# DSP2.net
KiCad netlist of a schematic drawn in Altium Designer
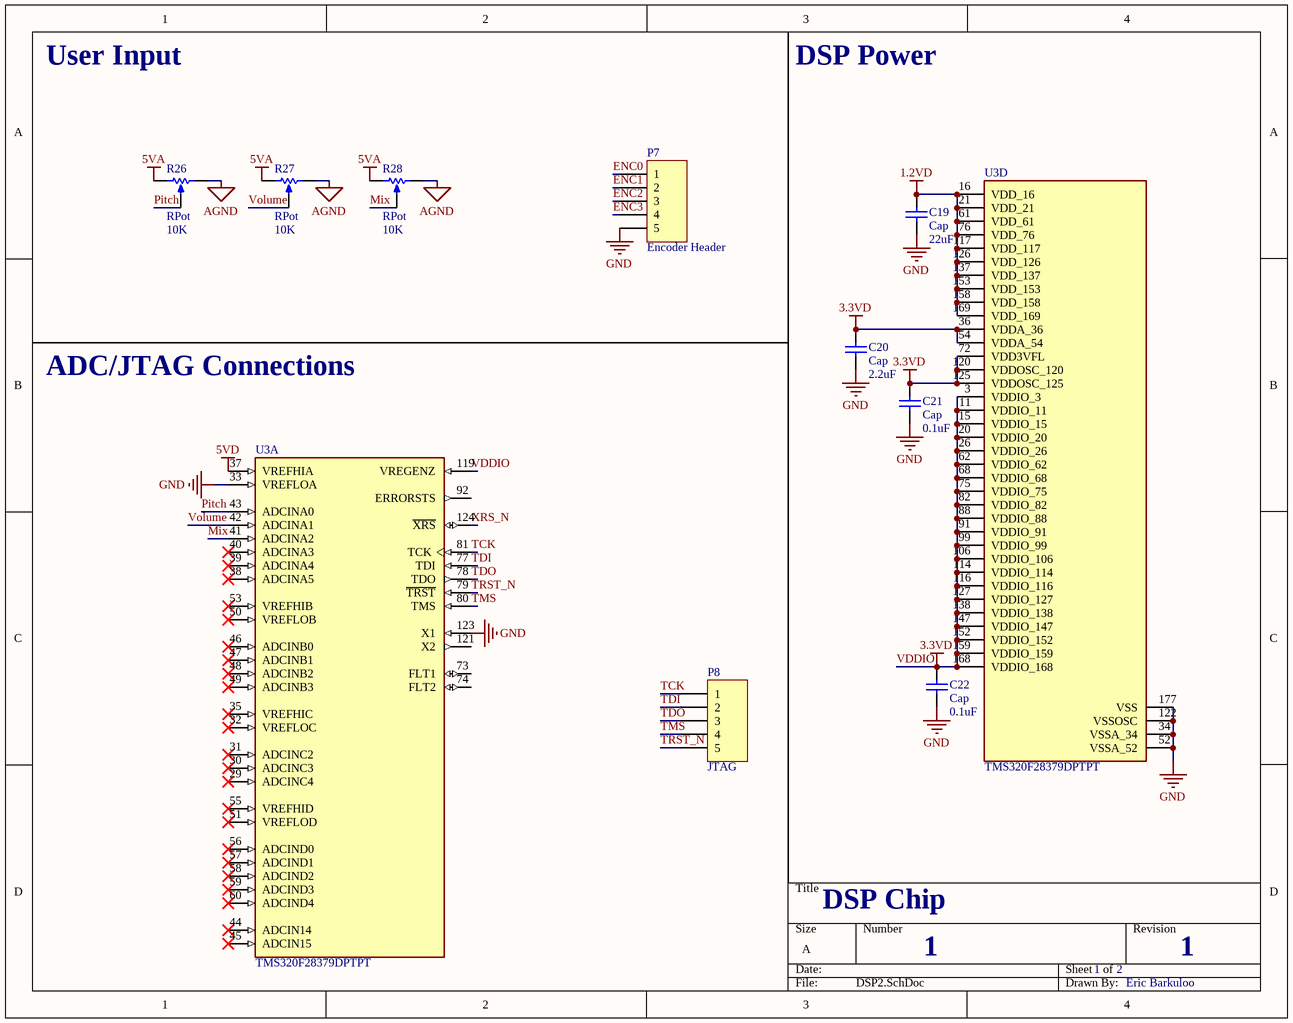
[diagram p0: DSP2.SchDoc]

(export (version "E")
  (design (tool "Eeschema 10.0.6"))
  (components
    (comp (ref "C19")
      (value "Cap")
      (footprint "RAD-0.3")
      (description "Capacitor")
      (fields (field (name "ALTIUM_VALUE") "22uF") (field (name "PUBLISHER") "Altium Limited"))
      (libsource (lib "Miscellaneous Devices") (part "Cap"))
    )
    (comp (ref "C20")
      (value "Cap")
      (footprint "RAD-0.3")
      (description "Capacitor")
      (fields (field (name "ALTIUM_VALUE") "2.2uF") (field (name "PUBLISHER") "Altium Limited"))
      (libsource (lib "Miscellaneous Devices") (part "Cap"))
    )
    (comp (ref "C21")
      (value "Cap")
      (footprint "RAD-0.3")
      (description "Capacitor")
      (fields (field (name "ALTIUM_VALUE") "0.1uF") (field (name "PUBLISHER") "Altium Limited"))
      (libsource (lib "Miscellaneous Devices") (part "Cap"))
    )
    (comp (ref "C22")
      (value "Cap")
      (footprint "RAD-0.3")
      (description "Capacitor")
      (fields (field (name "ALTIUM_VALUE") "0.1uF") (field (name "PUBLISHER") "Altium Limited"))
      (libsource (lib "Miscellaneous Devices") (part "Cap"))
    )
    (comp (ref "P7")
      (value "Encoder Header")
      (footprint "HDR1X5")
      (description "Header, 5-Pin")
      (fields (field (name "PUBLISHER") "Altium Limited"))
      (libsource (lib "Miscellaneous Connectors") (part "Header 5"))
    )
    (comp (ref "P8")
      (value "JTAG")
      (footprint "HDR1X5")
      (description "Header, 5-Pin")
      (fields (field (name "PUBLISHER") "Altium Limited"))
      (libsource (lib "Miscellaneous Connectors") (part "Header 5"))
    )
    (comp (ref "R26")
      (value "RPot")
      (footprint "VR5")
      (description "Potentiometer")
      (fields (field (name "ALTIUM_VALUE") "10K") (field (name "PUBLISHER") "Altium Limited"))
      (libsource (lib "Miscellaneous Devices") (part "RPot"))
    )
    (comp (ref "R27")
      (value "RPot")
      (footprint "VR5")
      (description "Potentiometer")
      (fields (field (name "ALTIUM_VALUE") "10K") (field (name "PUBLISHER") "Altium Limited"))
      (libsource (lib "Miscellaneous Devices") (part "RPot"))
    )
    (comp (ref "R28")
      (value "RPot")
      (footprint "VR5")
      (description "Potentiometer")
      (fields (field (name "ALTIUM_VALUE") "10K") (field (name "PUBLISHER") "Altium Limited"))
      (libsource (lib "Miscellaneous Devices") (part "RPot"))
    )
    (comp (ref "U3")
      (value "TMS320F28379DPTPT")
      (footprint "IC_TMS320F28379DPTPT")
      (libsource (lib "TMS320F28379DPTPT") (part "TMS320F28379DPTPT"))
    )
  )
  (nets
    (net (code "1") (name "/ENC0") (class "Default")
      (node (ref "P7") (pin "1") (pinfunction "1_1") (pintype "passive"))
    )
    (net (code "2") (name "/ENC1") (class "Default")
      (node (ref "P7") (pin "2") (pinfunction "2_2") (pintype "passive"))
    )
    (net (code "3") (name "/ENC2") (class "Default")
      (node (ref "P7") (pin "3") (pinfunction "3_3") (pintype "passive"))
    )
    (net (code "4") (name "/ENC3") (class "Default")
      (node (ref "P7") (pin "4") (pinfunction "4_4") (pintype "passive"))
    )
    (net (code "5") (name "/Mix") (class "Default")
      (node (ref "R28") (pin "3") (pinfunction "TAP_3") (pintype "passive"))
      (node (ref "U3") (pin "41") (pinfunction "ADCINA2_41") (pintype "input"))
    )
    (net (code "6") (name "/Pitch") (class "Default")
      (node (ref "R26") (pin "3") (pinfunction "TAP_3") (pintype "passive"))
      (node (ref "U3") (pin "43") (pinfunction "ADCINA0_43") (pintype "input"))
    )
    (net (code "7") (name "/TCK") (class "Default")
      (node (ref "P8") (pin "1") (pinfunction "1_1") (pintype "passive"))
      (node (ref "U3") (pin "81") (pinfunction "TCK_81") (pintype "input"))
    )
    (net (code "8") (name "/TDI") (class "Default")
      (node (ref "P8") (pin "2") (pinfunction "2_2") (pintype "passive"))
      (node (ref "U3") (pin "77") (pinfunction "TDI_77") (pintype "input"))
    )
    (net (code "9") (name "/TDO") (class "Default")
      (node (ref "P8") (pin "3") (pinfunction "3_3") (pintype "passive"))
      (node (ref "U3") (pin "78") (pinfunction "TDO_78") (pintype "output"))
    )
    (net (code "10") (name "/TMS") (class "Default")
      (node (ref "P8") (pin "4") (pinfunction "4_4") (pintype "passive"))
      (node (ref "U3") (pin "80") (pinfunction "TMS_80") (pintype "input"))
    )
    (net (code "11") (name "/TRST_N") (class "Default")
      (node (ref "P8") (pin "5") (pinfunction "5_5") (pintype "passive"))
      (node (ref "U3") (pin "79") (pinfunction "~{TRST}_79") (pintype "input"))
    )
    (net (code "12") (name "/Volume") (class "Default")
      (node (ref "R27") (pin "3") (pinfunction "TAP_3") (pintype "passive"))
      (node (ref "U3") (pin "42") (pinfunction "ADCINA1_42") (pintype "input"))
    )
    (net (code "13") (name "/XRS_N") (class "Default")
      (node (ref "U3") (pin "124") (pinfunction "~{XRS}_124") (pintype "bidirectional"))
    )
    (net (code "14") (name "1.2VD") (class "Default")
      (node (ref "C19") (pin "2") (pinfunction "2_2") (pintype "passive"))
      (node (ref "U3") (pin "117") (pinfunction "VDD_117_117") (pintype "power_in"))
      (node (ref "U3") (pin "126") (pinfunction "VDD_126_126") (pintype "power_in"))
      (node (ref "U3") (pin "137") (pinfunction "VDD_137_137") (pintype "power_in"))
      (node (ref "U3") (pin "153") (pinfunction "VDD_153_153") (pintype "power_in"))
      (node (ref "U3") (pin "158") (pinfunction "VDD_158_158") (pintype "power_in"))
      (node (ref "U3") (pin "16") (pinfunction "VDD_16_16") (pintype "power_in"))
      (node (ref "U3") (pin "169") (pinfunction "VDD_169_169") (pintype "power_in"))
      (node (ref "U3") (pin "21") (pinfunction "VDD_21_21") (pintype "power_in"))
      (node (ref "U3") (pin "61") (pinfunction "VDD_61_61") (pintype "power_in"))
      (node (ref "U3") (pin "76") (pinfunction "VDD_76_76") (pintype "power_in"))
    )
    (net (code "15") (name "3.3VD") (class "Default")
      (node (ref "C20") (pin "2") (pinfunction "2_2") (pintype "passive"))
      (node (ref "C21") (pin "2") (pinfunction "2_2") (pintype "passive"))
      (node (ref "C22") (pin "2") (pinfunction "2_2") (pintype "passive"))
      (node (ref "U3") (pin "106") (pinfunction "VDDIO_106_106") (pintype "power_in"))
      (node (ref "U3") (pin "11") (pinfunction "VDDIO_11_11") (pintype "power_in"))
      (node (ref "U3") (pin "114") (pinfunction "VDDIO_114_114") (pintype "power_in"))
      (node (ref "U3") (pin "116") (pinfunction "VDDIO_116_116") (pintype "power_in"))
      (node (ref "U3") (pin "119") (pinfunction "VREGENZ_119") (pintype "input"))
      (node (ref "U3") (pin "120") (pinfunction "VDDOSC_120_120") (pintype "power_in"))
      (node (ref "U3") (pin "125") (pinfunction "VDDOSC_125_125") (pintype "power_in"))
      (node (ref "U3") (pin "127") (pinfunction "VDDIO_127_127") (pintype "power_in"))
      (node (ref "U3") (pin "138") (pinfunction "VDDIO_138_138") (pintype "power_in"))
      (node (ref "U3") (pin "147") (pinfunction "VDDIO_147_147") (pintype "power_in"))
      (node (ref "U3") (pin "15") (pinfunction "VDDIO_15_15") (pintype "power_in"))
      (node (ref "U3") (pin "152") (pinfunction "VDDIO_152_152") (pintype "power_in"))
      (node (ref "U3") (pin "159") (pinfunction "VDDIO_159_159") (pintype "power_in"))
      (node (ref "U3") (pin "168") (pinfunction "VDDIO_168_168") (pintype "power_in"))
      (node (ref "U3") (pin "20") (pinfunction "VDDIO_20_20") (pintype "power_in"))
      (node (ref "U3") (pin "26") (pinfunction "VDDIO_26_26") (pintype "power_in"))
      (node (ref "U3") (pin "3") (pinfunction "VDDIO_3_3") (pintype "power_in"))
      (node (ref "U3") (pin "36") (pinfunction "VDDA_36_36") (pintype "power_in"))
      (node (ref "U3") (pin "54") (pinfunction "VDDA_54_54") (pintype "power_in"))
      (node (ref "U3") (pin "62") (pinfunction "VDDIO_62_62") (pintype "power_in"))
      (node (ref "U3") (pin "68") (pinfunction "VDDIO_68_68") (pintype "power_in"))
      (node (ref "U3") (pin "72") (pinfunction "VDD3VFL_72") (pintype "power_in"))
      (node (ref "U3") (pin "75") (pinfunction "VDDIO_75_75") (pintype "power_in"))
      (node (ref "U3") (pin "82") (pinfunction "VDDIO_82_82") (pintype "power_in"))
      (node (ref "U3") (pin "88") (pinfunction "VDDIO_88_88") (pintype "power_in"))
      (node (ref "U3") (pin "91") (pinfunction "VDDIO_91_91") (pintype "power_in"))
      (node (ref "U3") (pin "99") (pinfunction "VDDIO_99_99") (pintype "power_in"))
    )
    (net (code "16") (name "5VA") (class "Default")
      (node (ref "R26") (pin "1") (pinfunction "TOP_1") (pintype "passive"))
      (node (ref "R27") (pin "1") (pinfunction "TOP_1") (pintype "passive"))
      (node (ref "R28") (pin "1") (pinfunction "TOP_1") (pintype "passive"))
    )
    (net (code "17") (name "5VD") (class "Default")
      (node (ref "U3") (pin "37") (pinfunction "VREFHIA_37") (pintype "input"))
    )
    (net (code "18") (name "AGND") (class "Default")
      (node (ref "R26") (pin "2") (pinfunction "BOT_2") (pintype "passive"))
      (node (ref "R27") (pin "2") (pinfunction "BOT_2") (pintype "passive"))
      (node (ref "R28") (pin "2") (pinfunction "BOT_2") (pintype "passive"))
    )
    (net (code "19") (name "GND") (class "Default")
      (node (ref "C19") (pin "1") (pinfunction "1_1") (pintype "passive"))
      (node (ref "C20") (pin "1") (pinfunction "1_1") (pintype "passive"))
      (node (ref "C21") (pin "1") (pinfunction "1_1") (pintype "passive"))
      (node (ref "C22") (pin "1") (pinfunction "1_1") (pintype "passive"))
      (node (ref "P7") (pin "5") (pinfunction "5_5") (pintype "passive"))
      (node (ref "U3") (pin "122") (pinfunction "VSSOSC_122") (pintype "power_in"))
      (node (ref "U3") (pin "123") (pinfunction "X1_123") (pintype "input"))
      (node (ref "U3") (pin "177") (pinfunction "VSS_177") (pintype "power_in"))
      (node (ref "U3") (pin "33") (pinfunction "VREFLOA_33") (pintype "input"))
      (node (ref "U3") (pin "34") (pinfunction "VSSA_34_34") (pintype "power_in"))
      (node (ref "U3") (pin "52") (pinfunction "VSSA_52_52") (pintype "power_in"))
    )
    (net (code "20") (name "unconnected-(U3A-ADCIN14-Pad44)") (class "Default")
      (node (ref "U3") (pin "44") (pinfunction "ADCIN14_44") (pintype "input+no_connect"))
    )
    (net (code "21") (name "unconnected-(U3A-ADCIN15-Pad45)") (class "Default")
      (node (ref "U3") (pin "45") (pinfunction "ADCIN15_45") (pintype "input+no_connect"))
    )
    (net (code "22") (name "unconnected-(U3A-ADCINA3-Pad40)") (class "Default")
      (node (ref "U3") (pin "40") (pinfunction "ADCINA3_40") (pintype "input+no_connect"))
    )
    (net (code "23") (name "unconnected-(U3A-ADCINA4-Pad39)") (class "Default")
      (node (ref "U3") (pin "39") (pinfunction "ADCINA4_39") (pintype "input+no_connect"))
    )
    (net (code "24") (name "unconnected-(U3A-ADCINA5-Pad38)") (class "Default")
      (node (ref "U3") (pin "38") (pinfunction "ADCINA5_38") (pintype "input+no_connect"))
    )
    (net (code "25") (name "unconnected-(U3A-ADCINB0-Pad46)") (class "Default")
      (node (ref "U3") (pin "46") (pinfunction "ADCINB0_46") (pintype "input+no_connect"))
    )
    (net (code "26") (name "unconnected-(U3A-ADCINB1-Pad47)") (class "Default")
      (node (ref "U3") (pin "47") (pinfunction "ADCINB1_47") (pintype "input+no_connect"))
    )
    (net (code "27") (name "unconnected-(U3A-ADCINB2-Pad48)") (class "Default")
      (node (ref "U3") (pin "48") (pinfunction "ADCINB2_48") (pintype "input+no_connect"))
    )
    (net (code "28") (name "unconnected-(U3A-ADCINB3-Pad49)") (class "Default")
      (node (ref "U3") (pin "49") (pinfunction "ADCINB3_49") (pintype "input+no_connect"))
    )
    (net (code "29") (name "unconnected-(U3A-ADCINC2-Pad31)") (class "Default")
      (node (ref "U3") (pin "31") (pinfunction "ADCINC2_31") (pintype "input+no_connect"))
    )
    (net (code "30") (name "unconnected-(U3A-ADCINC3-Pad30)") (class "Default")
      (node (ref "U3") (pin "30") (pinfunction "ADCINC3_30") (pintype "input+no_connect"))
    )
    (net (code "31") (name "unconnected-(U3A-ADCINC4-Pad29)") (class "Default")
      (node (ref "U3") (pin "29") (pinfunction "ADCINC4_29") (pintype "input+no_connect"))
    )
    (net (code "32") (name "unconnected-(U3A-ADCIND0-Pad56)") (class "Default")
      (node (ref "U3") (pin "56") (pinfunction "ADCIND0_56") (pintype "input+no_connect"))
    )
    (net (code "33") (name "unconnected-(U3A-ADCIND1-Pad57)") (class "Default")
      (node (ref "U3") (pin "57") (pinfunction "ADCIND1_57") (pintype "input+no_connect"))
    )
    (net (code "34") (name "unconnected-(U3A-ADCIND2-Pad58)") (class "Default")
      (node (ref "U3") (pin "58") (pinfunction "ADCIND2_58") (pintype "input+no_connect"))
    )
    (net (code "35") (name "unconnected-(U3A-ADCIND3-Pad59)") (class "Default")
      (node (ref "U3") (pin "59") (pinfunction "ADCIND3_59") (pintype "input+no_connect"))
    )
    (net (code "36") (name "unconnected-(U3A-ADCIND4-Pad60)") (class "Default")
      (node (ref "U3") (pin "60") (pinfunction "ADCIND4_60") (pintype "input+no_connect"))
    )
    (net (code "37") (name "unconnected-(U3A-ERRORSTS-Pad92)") (class "Default")
      (node (ref "U3") (pin "92") (pinfunction "ERRORSTS_92") (pintype "output"))
    )
    (net (code "38") (name "unconnected-(U3A-FLT1-Pad73)") (class "Default")
      (node (ref "U3") (pin "73") (pinfunction "FLT1_73") (pintype "bidirectional"))
    )
    (net (code "39") (name "unconnected-(U3A-FLT2-Pad74)") (class "Default")
      (node (ref "U3") (pin "74") (pinfunction "FLT2_74") (pintype "bidirectional"))
    )
    (net (code "40") (name "unconnected-(U3A-VREFHIB-Pad53)") (class "Default")
      (node (ref "U3") (pin "53") (pinfunction "VREFHIB_53") (pintype "input+no_connect"))
    )
    (net (code "41") (name "unconnected-(U3A-VREFHIC-Pad35)") (class "Default")
      (node (ref "U3") (pin "35") (pinfunction "VREFHIC_35") (pintype "input+no_connect"))
    )
    (net (code "42") (name "unconnected-(U3A-VREFHID-Pad55)") (class "Default")
      (node (ref "U3") (pin "55") (pinfunction "VREFHID_55") (pintype "input+no_connect"))
    )
    (net (code "43") (name "unconnected-(U3A-VREFLOB-Pad50)") (class "Default")
      (node (ref "U3") (pin "50") (pinfunction "VREFLOB_50") (pintype "input+no_connect"))
    )
    (net (code "44") (name "unconnected-(U3A-VREFLOC-Pad32)") (class "Default")
      (node (ref "U3") (pin "32") (pinfunction "VREFLOC_32") (pintype "input+no_connect"))
    )
    (net (code "45") (name "unconnected-(U3A-VREFLOD-Pad51)") (class "Default")
      (node (ref "U3") (pin "51") (pinfunction "VREFLOD_51") (pintype "input+no_connect"))
    )
    (net (code "46") (name "unconnected-(U3A-X2-Pad121)") (class "Default")
      (node (ref "U3") (pin "121") (pinfunction "X2_121") (pintype "output"))
    )
  )
)
